# LEDs.net
KiCad netlist of a schematic drawn in Altium Designer
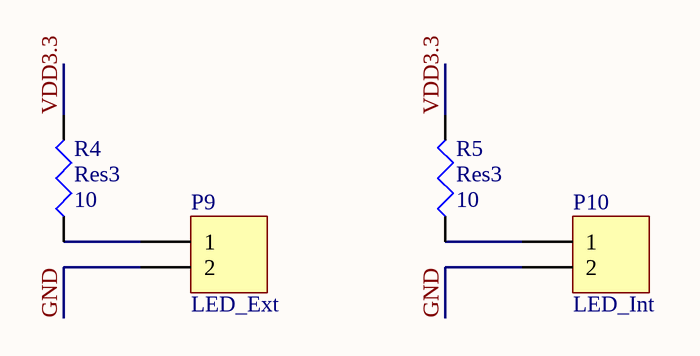
[diagram p0: LEDs.SchDoc]

(export (version "E")
  (design (tool "Eeschema 10.0.6"))
  (components
    (comp (ref "P9")
      (value "LED_Ext")
      (footprint "HDR1X2")
      (description "Header, 2-Pin")
      (fields (field (name "PUBLISHER") "Altium Limited"))
      (libsource (lib "Miscellaneous Connectors") (part "Header 2"))
    )
    (comp (ref "P10")
      (value "LED_Int")
      (footprint "HDR1X2")
      (description "Header, 2-Pin")
      (fields (field (name "PUBLISHER") "Altium Limited"))
      (libsource (lib "Miscellaneous Connectors") (part "Header 2"))
    )
    (comp (ref "R4")
      (value "Res3")
      (footprint "J1-0603")
      (description "Resistor")
      (fields (field (name "ALTIUM_VALUE") "10") (field (name "PUBLISHER") "Altium Limited"))
      (libsource (lib "Miscellaneous Devices") (part "Res3"))
    )
    (comp (ref "R5")
      (value "Res3")
      (footprint "J1-0603")
      (description "Resistor")
      (fields (field (name "ALTIUM_VALUE") "10") (field (name "PUBLISHER") "Altium Limited"))
      (libsource (lib "Miscellaneous Devices") (part "Res3"))
    )
  )
  (nets
    (net (code "1") (name "/GND") (class "Default")
      (node (ref "P10") (pin "2") (pinfunction "2_2") (pintype "passive"))
      (node (ref "P9") (pin "2") (pinfunction "2_2") (pintype "passive"))
    )
    (net (code "2") (name "/VDD3.3") (class "Default")
      (node (ref "R4") (pin "2") (pinfunction "2_2") (pintype "passive"))
      (node (ref "R5") (pin "2") (pinfunction "2_2") (pintype "passive"))
    )
    (net (code "3") (name "Net-(P9-Pad1)") (class "Default")
      (node (ref "P9") (pin "1") (pinfunction "1_1") (pintype "passive"))
      (node (ref "R4") (pin "1") (pinfunction "1_1") (pintype "passive"))
    )
    (net (code "4") (name "Net-(P10-Pad1)") (class "Default")
      (node (ref "P10") (pin "1") (pinfunction "1_1") (pintype "passive"))
      (node (ref "R5") (pin "1") (pinfunction "1_1") (pintype "passive"))
    )
  )
)
